# 780-00055_rev1_Pg3_SCH_NRES_Temp_Meas_8-.net
KiCad netlist of a schematic drawn in Altium Designer
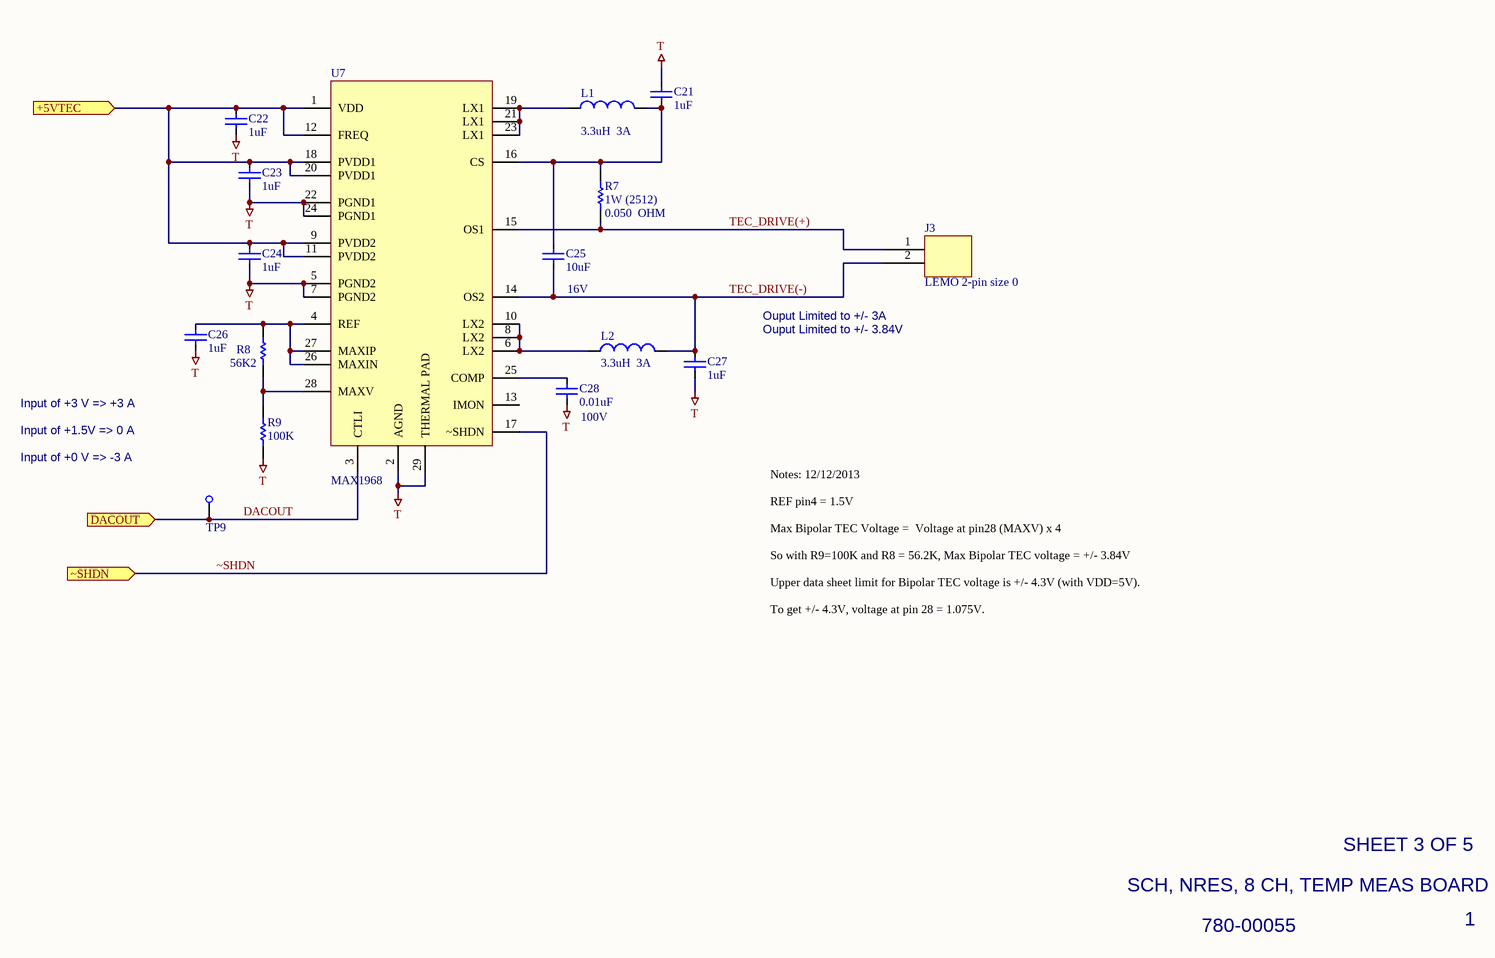
[diagram p0: 780-00055, rev1, Pg3, SCH, NRES Temp Meas, 8-Chan RTD .SchDoc]

(export (version "E")
  (design (tool "Eeschema 10.0.6"))
  (components
    (comp (ref "C21")
      (value "1uF")
      (footprint "SMD_0805")
      (description "Capacitor")
      (fields (field (name "Comment") "Cap SMD"))
      (libsource (lib "Richs Schematic Components") (part "Cap SMD"))
    )
    (comp (ref "C22")
      (value "1uF")
      (footprint "SMD_0805")
      (description "Capacitor")
      (fields (field (name "Comment") "Cap SMD"))
      (libsource (lib "Richs Schematic Components") (part "Cap SMD"))
    )
    (comp (ref "C23")
      (value "1uF")
      (footprint "SMD_0805")
      (description "Capacitor")
      (fields (field (name "Comment") "Cap SMD"))
      (libsource (lib "Richs Schematic Components") (part "Cap SMD"))
    )
    (comp (ref "C24")
      (value "1uF")
      (footprint "SMD_0805")
      (description "Capacitor")
      (fields (field (name "Comment") "Cap SMD"))
      (libsource (lib "Richs Schematic Components") (part "Cap SMD"))
    )
    (comp (ref "C25")
      (value "16V")
      (footprint "SMD_0805")
      (description "Capacitor")
      (fields (field (name "ALTIUM_VALUE") "10uF"))
      (libsource (lib "Richs Schematic Components") (part "Cap SMD"))
    )
    (comp (ref "C26")
      (value "1uF")
      (footprint "SMD_0805")
      (description "Capacitor")
      (fields (field (name "Comment") "Cap SMD"))
      (libsource (lib "Richs Schematic Components") (part "Cap SMD"))
    )
    (comp (ref "C27")
      (value "1uF")
      (footprint "SMD_0805")
      (description "Capacitor")
      (fields (field (name "Comment") "Cap SMD"))
      (libsource (lib "Richs Schematic Components") (part "Cap SMD"))
    )
    (comp (ref "C28")
      (value "100V")
      (footprint "SMD_0805")
      (description "Capacitor")
      (fields (field (name "MANUFACTURER") "Johanson") (field (name "ALTIUM_VALUE") "0.01uF"))
      (libsource (lib "Richs Schematic Components") (part "Cap SMD"))
    )
    (comp (ref "J3")
      (value "LEMO 2-pin size 0")
      (footprint "LEMO Size 0, 2-pin PCB")
      (libsource (lib "Richs Schematic Components") (part "LEMO Size 0, 2 pin, PCB"))
    )
    (comp (ref "L1")
      (value "3.3uH  3A")
      (footprint "SMT Inductor 7 x 7mm")
      (description "Inductor")
      (fields (field (name "MANUFACTURER") "Coiltronics") (field (name "Comment") "513-1481-2-ND"))
      (libsource (lib "Richs Schematic Components") (part "Inductor SMD 7 x 7mm"))
    )
    (comp (ref "L2")
      (value "3.3uH  3A")
      (footprint "SMT Inductor 7 x 7mm")
      (description "Inductor")
      (fields (field (name "MANUFACTURER") "Coiltronics") (field (name "Comment") "513-1481-2-ND"))
      (libsource (lib "Richs Schematic Components") (part "Inductor SMD 7 x 7mm"))
    )
    (comp (ref "R7")
      (value "1W (2512)")
      (footprint "6332[2512]")
      (fields (field (name "MANUFACTURER") "Panasonic") (field (name "ALTIUM_VALUE") "0.050  OHM"))
      (libsource (lib "Richs Schematic Components") (part "Res SMD"))
    )
    (comp (ref "R8")
      (value "56K2")
      (footprint "SMD_0805")
      (description "Resistor 0805")
      (fields (field (name "MANUFACTURER") "Vishay/Dale") (field (name "Comment") "Res 0805"))
      (libsource (lib "Richs Schematic Components") (part "Res SMD"))
    )
    (comp (ref "R9")
      (value "100K")
      (footprint "SMD_0805")
      (description "Resistor 0805")
      (fields (field (name "MANUFACTURER") "Vishay/Dale") (field (name "Comment") "Res 0805"))
      (libsource (lib "Richs Schematic Components") (part "Res SMD"))
    )
    (comp (ref "TP9")
      (value "Test point")
      (footprint "Protel 99SE BANKS PCB:PAD_80D_052H")
      (description "Test Point")
      (fields (field (name "MANUFACTURER") "Keystone"))
      (libsource (lib "Richs Schematic Components") (part "Test point"))
    )
    (comp (ref "U7")
      (value "MAX1968")
      (footprint "TSSOP28 Exposed Pad")
      (description "TEC Driver +/- 3A")
      (fields (field (name "MANUFACTURER") "Maxim"))
      (libsource (lib "Richs Schematic Components") (part "MAX1968"))
    )
  )
  (nets
    (net (code "1") (name "/+5VTEC") (class "Default")
      (node (ref "C22") (pin "2") (pinfunction "2_2") (pintype "passive"))
      (node (ref "C23") (pin "2") (pinfunction "2_2") (pintype "passive"))
      (node (ref "C24") (pin "2") (pinfunction "2_2") (pintype "passive"))
      (node (ref "U7") (pin "1") (pinfunction "VDD_1") (pintype "passive"))
      (node (ref "U7") (pin "11") (pinfunction "PVDD2_11") (pintype "passive"))
      (node (ref "U7") (pin "12") (pinfunction "FREQ_12") (pintype "passive"))
      (node (ref "U7") (pin "18") (pinfunction "PVDD1_18") (pintype "passive"))
      (node (ref "U7") (pin "20") (pinfunction "PVDD1_20") (pintype "passive"))
      (node (ref "U7") (pin "9") (pinfunction "PVDD2_9") (pintype "passive"))
    )
    (net (code "2") (name "/DACOUT") (class "Default")
      (node (ref "TP9") (pin "1") (pinfunction "TP_1") (pintype "passive"))
      (node (ref "U7") (pin "3") (pinfunction "CTLI_3") (pintype "passive"))
    )
    (net (code "3") (name "/TEC_DRIVE(+)") (class "Default")
      (node (ref "J3") (pin "1") (pinfunction "S29_1") (pintype "passive"))
      (node (ref "R7") (pin "1") (pinfunction "1_1") (pintype "passive"))
      (node (ref "U7") (pin "15") (pinfunction "OS1_15") (pintype "passive"))
    )
    (net (code "4") (name "/TEC_DRIVE(-)") (class "Default")
      (node (ref "C25") (pin "1") (pinfunction "1_1") (pintype "passive"))
      (node (ref "C27") (pin "2") (pinfunction "2_2") (pintype "passive"))
      (node (ref "J3") (pin "2") (pinfunction "S30_2") (pintype "passive"))
      (node (ref "L2") (pin "2") (pinfunction "2_2") (pintype "passive"))
      (node (ref "U7") (pin "14") (pinfunction "OS2_14") (pintype "passive"))
    )
    (net (code "5") (name "/~SHDN") (class "Default")
      (node (ref "U7") (pin "17") (pinfunction "~SHDN_17") (pintype "passive"))
    )
    (net (code "6") (name "Net-(L1-Pad1)") (class "Default")
      (node (ref "L1") (pin "1") (pinfunction "1_1") (pintype "passive"))
      (node (ref "U7") (pin "19") (pinfunction "LX1_19") (pintype "passive"))
      (node (ref "U7") (pin "21") (pinfunction "LX1_21") (pintype "passive"))
      (node (ref "U7") (pin "23") (pinfunction "LX1_23") (pintype "passive"))
    )
    (net (code "7") (name "Net-(L2-Pad1)") (class "Default")
      (node (ref "L2") (pin "1") (pinfunction "1_1") (pintype "passive"))
      (node (ref "U7") (pin "10") (pinfunction "LX2_10") (pintype "passive"))
      (node (ref "U7") (pin "6") (pinfunction "LX2_6") (pintype "passive"))
      (node (ref "U7") (pin "8") (pinfunction "LX2_8") (pintype "passive"))
    )
    (net (code "8") (name "Net-(U7-COMP)") (class "Default")
      (node (ref "C28") (pin "2") (pinfunction "2_2") (pintype "passive"))
      (node (ref "U7") (pin "25") (pinfunction "COMP_25") (pintype "passive"))
    )
    (net (code "9") (name "Net-(U7-CS)") (class "Default")
      (node (ref "C21") (pin "1") (pinfunction "1_1") (pintype "passive"))
      (node (ref "C25") (pin "2") (pinfunction "2_2") (pintype "passive"))
      (node (ref "L1") (pin "2") (pinfunction "2_2") (pintype "passive"))
      (node (ref "R7") (pin "2") (pinfunction "2_2") (pintype "passive"))
      (node (ref "U7") (pin "16") (pinfunction "CS_16") (pintype "passive"))
    )
    (net (code "10") (name "Net-(U7-MAXIN)") (class "Default")
      (node (ref "C26") (pin "2") (pinfunction "2_2") (pintype "passive"))
      (node (ref "R8") (pin "2") (pinfunction "2_2") (pintype "passive"))
      (node (ref "U7") (pin "26") (pinfunction "MAXIN_26") (pintype "passive"))
      (node (ref "U7") (pin "27") (pinfunction "MAXIP_27") (pintype "passive"))
      (node (ref "U7") (pin "4") (pinfunction "REF_4") (pintype "passive"))
    )
    (net (code "11") (name "Net-(U7-MAXV)") (class "Default")
      (node (ref "R8") (pin "1") (pinfunction "1_1") (pintype "passive"))
      (node (ref "R9") (pin "2") (pinfunction "2_2") (pintype "passive"))
      (node (ref "U7") (pin "28") (pinfunction "MAXV_28") (pintype "passive"))
    )
    (net (code "12") (name "T") (class "Default")
      (node (ref "C21") (pin "2") (pinfunction "2_2") (pintype "passive"))
      (node (ref "C22") (pin "1") (pinfunction "1_1") (pintype "passive"))
      (node (ref "C23") (pin "1") (pinfunction "1_1") (pintype "passive"))
      (node (ref "C24") (pin "1") (pinfunction "1_1") (pintype "passive"))
      (node (ref "C26") (pin "1") (pinfunction "1_1") (pintype "passive"))
      (node (ref "C27") (pin "1") (pinfunction "1_1") (pintype "passive"))
      (node (ref "C28") (pin "1") (pinfunction "1_1") (pintype "passive"))
      (node (ref "R9") (pin "1") (pinfunction "1_1") (pintype "passive"))
      (node (ref "U7") (pin "2") (pinfunction "AGND_2") (pintype "passive"))
      (node (ref "U7") (pin "22") (pinfunction "PGND1_22") (pintype "passive"))
      (node (ref "U7") (pin "24") (pinfunction "PGND1_24") (pintype "passive"))
      (node (ref "U7") (pin "29") (pinfunction "THERMAL_PAD_29") (pintype "passive"))
      (node (ref "U7") (pin "5") (pinfunction "PGND2_5") (pintype "passive"))
      (node (ref "U7") (pin "7") (pinfunction "PGND2_7") (pintype "passive"))
    )
    (net (code "13") (name "unconnected-(U7-IMON-Pad13)") (class "Default")
      (node (ref "U7") (pin "13") (pinfunction "IMON_13") (pintype "passive"))
    )
  )
)
